# Step_2_0.net
KiCad netlist of a schematic drawn in EAGLE
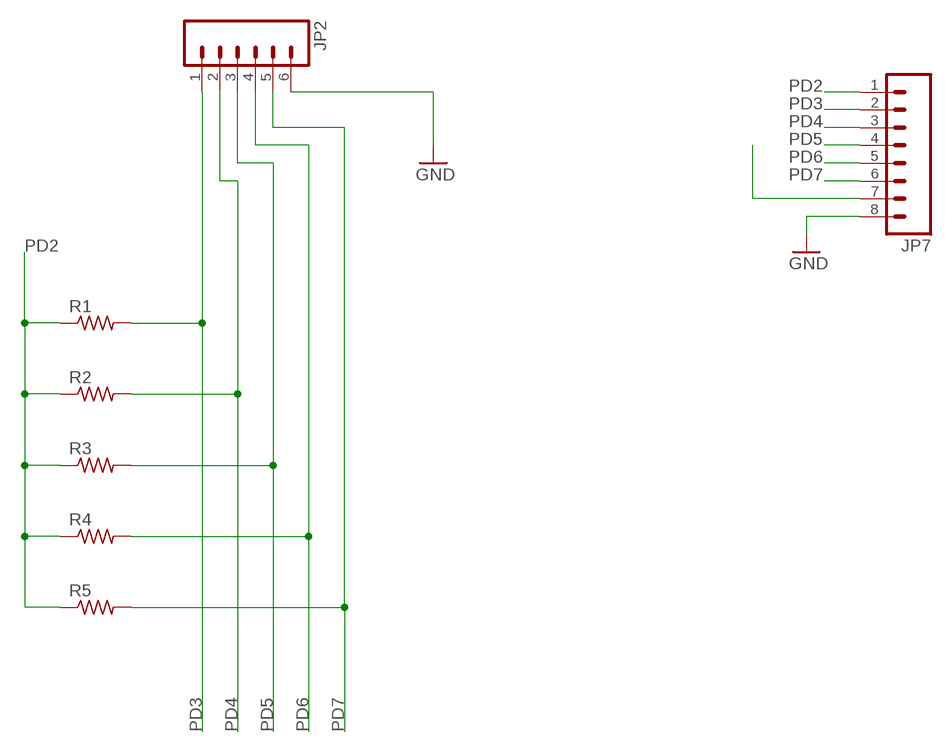
[diagram p0: schematic, sheet 1]

(export (version "E")
  (design (tool "Eeschema 10.0.6"))
  (components
    (comp (ref "JP2")
      (value "M06SIP")
      (footprint "eagle-import:1X06")
      (libsource (lib "eagle-import") (part "M06SIP"))
    )
    (comp (ref "JP7")
      (value "M08")
      (footprint "eagle-import:1X08")
      (libsource (lib "eagle-import") (part "M08"))
    )
    (comp (ref "R1")
      (value "RESISTOR1206")
      (footprint "eagle-import:1206")
      (libsource (lib "eagle-import") (part "RESISTOR1206"))
    )
    (comp (ref "R2")
      (value "RESISTOR1206")
      (footprint "eagle-import:1206")
      (libsource (lib "eagle-import") (part "RESISTOR1206"))
    )
    (comp (ref "R3")
      (value "RESISTOR1206")
      (footprint "eagle-import:1206")
      (libsource (lib "eagle-import") (part "RESISTOR1206"))
    )
    (comp (ref "R4")
      (value "RESISTOR1206")
      (footprint "eagle-import:1206")
      (libsource (lib "eagle-import") (part "RESISTOR1206"))
    )
    (comp (ref "R5")
      (value "RESISTOR1206")
      (footprint "eagle-import:1206")
      (libsource (lib "eagle-import") (part "RESISTOR1206"))
    )
  )
  (nets
    (net (code "1") (name "/PD2") (class "Default")
      (node (ref "JP7") (pin "1") (pinfunction "1_1") (pintype "passive"))
      (node (ref "R1") (pin "1") (pinfunction "1_1") (pintype "passive"))
      (node (ref "R2") (pin "1") (pinfunction "1_1") (pintype "passive"))
      (node (ref "R3") (pin "1") (pinfunction "1_1") (pintype "passive"))
      (node (ref "R4") (pin "1") (pinfunction "1_1") (pintype "passive"))
      (node (ref "R5") (pin "1") (pinfunction "1_1") (pintype "passive"))
    )
    (net (code "2") (name "/PD3") (class "Default")
      (node (ref "JP2") (pin "1") (pinfunction "1_1") (pintype "passive"))
      (node (ref "JP7") (pin "2") (pinfunction "2_2") (pintype "passive"))
      (node (ref "R1") (pin "2") (pinfunction "2_2") (pintype "passive"))
    )
    (net (code "3") (name "/PD4") (class "Default")
      (node (ref "JP2") (pin "2") (pinfunction "2_2") (pintype "passive"))
      (node (ref "JP7") (pin "3") (pinfunction "3_3") (pintype "passive"))
      (node (ref "R2") (pin "2") (pinfunction "2_2") (pintype "passive"))
    )
    (net (code "4") (name "/PD5") (class "Default")
      (node (ref "JP2") (pin "3") (pinfunction "3_3") (pintype "passive"))
      (node (ref "JP7") (pin "4") (pinfunction "4_4") (pintype "passive"))
      (node (ref "R3") (pin "2") (pinfunction "2_2") (pintype "passive"))
    )
    (net (code "5") (name "/PD6") (class "Default")
      (node (ref "JP2") (pin "4") (pinfunction "4_4") (pintype "passive"))
      (node (ref "JP7") (pin "5") (pinfunction "5_5") (pintype "passive"))
      (node (ref "R4") (pin "2") (pinfunction "2_2") (pintype "passive"))
    )
    (net (code "6") (name "/PD7") (class "Default")
      (node (ref "JP2") (pin "5") (pinfunction "5_5") (pintype "passive"))
      (node (ref "JP7") (pin "6") (pinfunction "6_6") (pintype "passive"))
      (node (ref "R5") (pin "2") (pinfunction "2_2") (pintype "passive"))
    )
    (net (code "7") (name "GND") (class "Default")
      (node (ref "JP2") (pin "6") (pinfunction "6_6") (pintype "passive"))
      (node (ref "JP7") (pin "8") (pinfunction "8_8") (pintype "passive"))
    )
    (net (code "8") (name "unconnected-(JP7-Pad7)") (class "Default")
      (node (ref "JP7") (pin "7") (pinfunction "7_7") (pintype "passive"))
    )
  )
)
